# haptic_knob.net
KiCad netlist of a schematic drawn in EasyEDA Pro
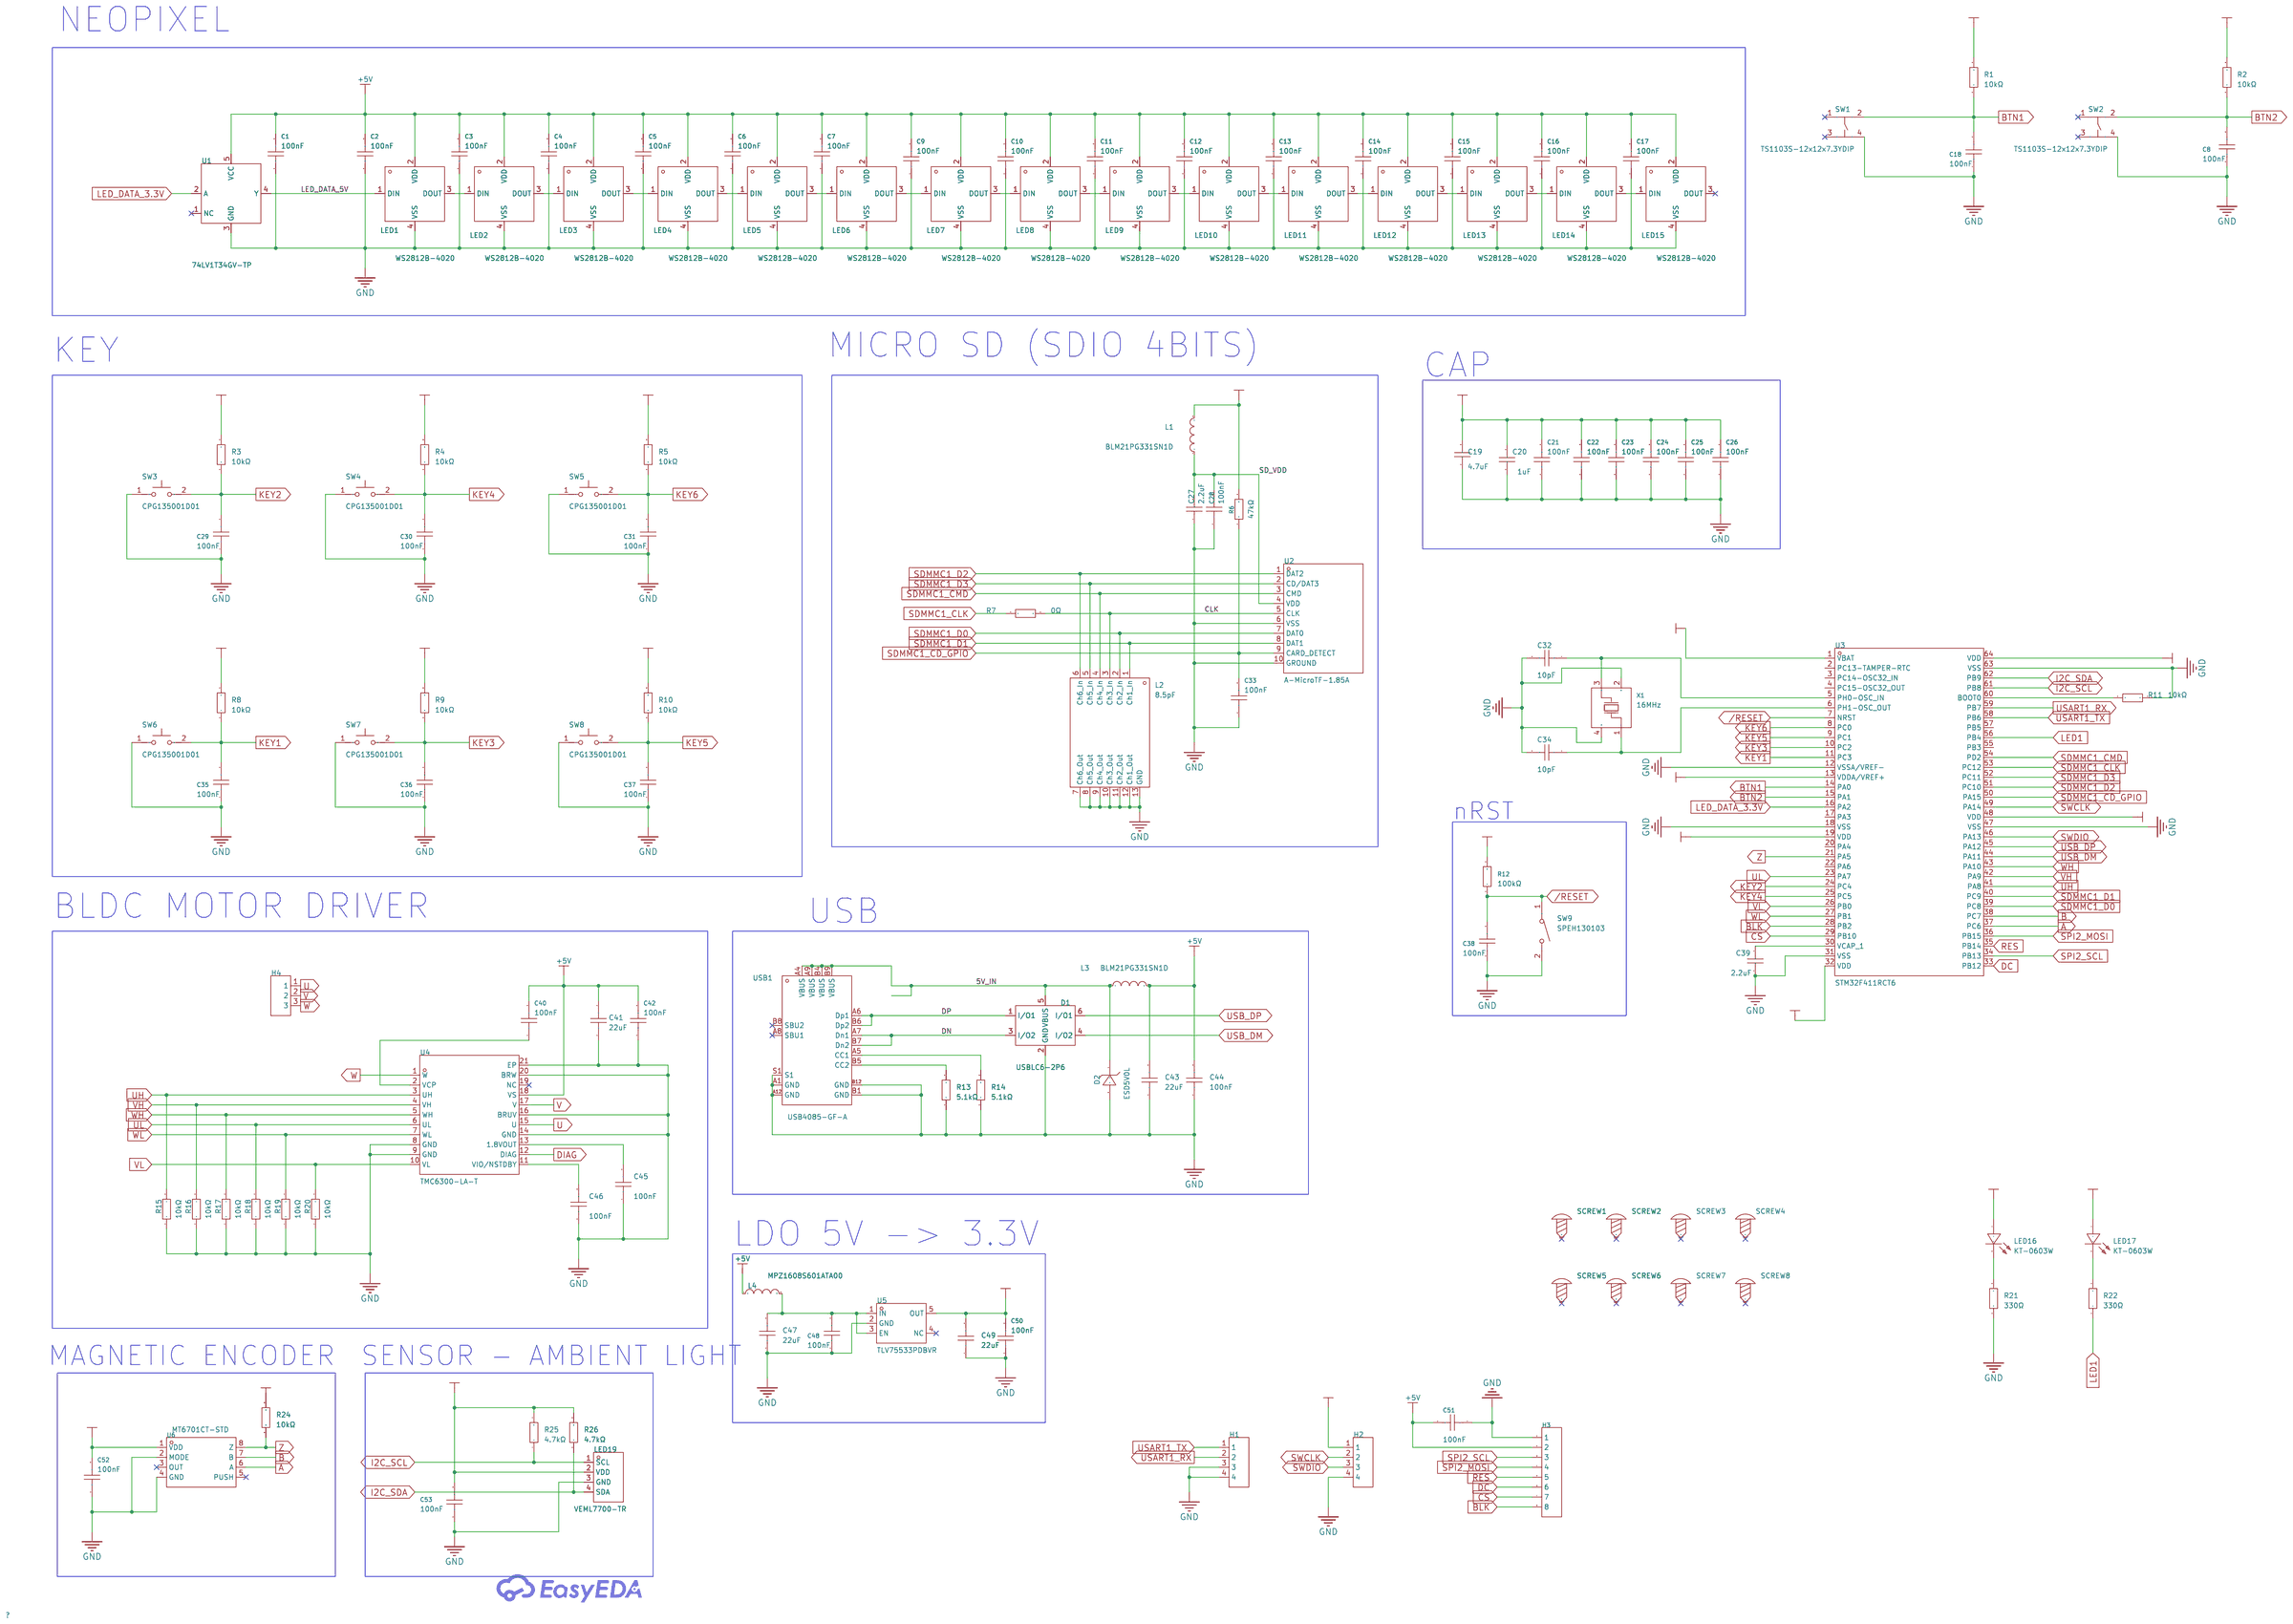
[diagram p0: schematic sheet]

(export (version "E")
  (design (tool "Eeschema 10.0.6"))
  (components
    (comp (ref "C1")
      (value "100nF")
      (fields
        (field (name "Manufacturer Part") "CC0603KRX7R9BB104")
        (field (name "Manufacturer") "YAGEO(国巨)")
      )
      (libsource (lib "easyedapro") (part "CL10B104KB8NNNC"))
    )
    (comp (ref "C2")
      (value "100nF")
      (fields
        (field (name "Manufacturer Part") "CC0603KRX7R9BB104")
        (field (name "Manufacturer") "YAGEO(国巨)")
      )
      (libsource (lib "easyedapro") (part "CL10B104KB8NNNC"))
    )
    (comp (ref "C3")
      (value "100nF")
      (fields
        (field (name "Manufacturer Part") "CC0603KRX7R9BB104")
        (field (name "Manufacturer") "YAGEO(国巨)")
      )
      (libsource (lib "easyedapro") (part "CL10B104KB8NNNC"))
    )
    (comp (ref "C4")
      (value "100nF")
      (fields
        (field (name "Manufacturer Part") "CC0603KRX7R9BB104")
        (field (name "Manufacturer") "YAGEO(国巨)")
      )
      (libsource (lib "easyedapro") (part "CL10B104KB8NNNC"))
    )
    (comp (ref "C5")
      (value "100nF")
      (fields
        (field (name "Manufacturer Part") "CC0603KRX7R9BB104")
        (field (name "Manufacturer") "YAGEO(国巨)")
      )
      (libsource (lib "easyedapro") (part "CL10B104KB8NNNC"))
    )
    (comp (ref "C6")
      (value "100nF")
      (fields
        (field (name "Manufacturer Part") "CC0603KRX7R9BB104")
        (field (name "Manufacturer") "YAGEO(国巨)")
      )
      (libsource (lib "easyedapro") (part "CL10B104KB8NNNC"))
    )
    (comp (ref "C7")
      (value "100nF")
      (fields
        (field (name "Manufacturer Part") "CC0603KRX7R9BB104")
        (field (name "Manufacturer") "YAGEO(国巨)")
      )
      (libsource (lib "easyedapro") (part "CL10B104KB8NNNC"))
    )
    (comp (ref "C8")
      (value "100nF")
      (fields
        (field (name "Manufacturer Part") "CC0603KRX7R9BB104")
        (field (name "Manufacturer") "YAGEO(国巨)")
      )
      (libsource (lib "easyedapro") (part "CL10B104KB8NNNC"))
    )
    (comp (ref "C9")
      (value "100nF")
      (fields
        (field (name "Manufacturer Part") "CC0603KRX7R9BB104")
        (field (name "Manufacturer") "YAGEO(国巨)")
      )
      (libsource (lib "easyedapro") (part "CL10B104KB8NNNC"))
    )
    (comp (ref "C10")
      (value "100nF")
      (fields
        (field (name "Manufacturer Part") "CC0603KRX7R9BB104")
        (field (name "Manufacturer") "YAGEO(国巨)")
      )
      (libsource (lib "easyedapro") (part "CL10B104KB8NNNC"))
    )
    (comp (ref "C11")
      (value "100nF")
      (fields
        (field (name "Manufacturer Part") "CC0603KRX7R9BB104")
        (field (name "Manufacturer") "YAGEO(国巨)")
      )
      (libsource (lib "easyedapro") (part "CL10B104KB8NNNC"))
    )
    (comp (ref "C12")
      (value "100nF")
      (fields
        (field (name "Manufacturer Part") "CC0603KRX7R9BB104")
        (field (name "Manufacturer") "YAGEO(国巨)")
      )
      (libsource (lib "easyedapro") (part "CL10B104KB8NNNC"))
    )
    (comp (ref "C13")
      (value "100nF")
      (fields
        (field (name "Manufacturer Part") "CC0603KRX7R9BB104")
        (field (name "Manufacturer") "YAGEO(国巨)")
      )
      (libsource (lib "easyedapro") (part "CL10B104KB8NNNC"))
    )
    (comp (ref "C14")
      (value "100nF")
      (fields
        (field (name "Manufacturer Part") "CC0603KRX7R9BB104")
        (field (name "Manufacturer") "YAGEO(国巨)")
      )
      (libsource (lib "easyedapro") (part "CL10B104KB8NNNC"))
    )
    (comp (ref "C15")
      (value "100nF")
      (fields
        (field (name "Manufacturer Part") "CC0603KRX7R9BB104")
        (field (name "Manufacturer") "YAGEO(国巨)")
      )
      (libsource (lib "easyedapro") (part "CL10B104KB8NNNC"))
    )
    (comp (ref "C16")
      (value "100nF")
      (fields
        (field (name "Manufacturer Part") "CC0603KRX7R9BB104")
        (field (name "Manufacturer") "YAGEO(国巨)")
      )
      (libsource (lib "easyedapro") (part "CL10B104KB8NNNC"))
    )
    (comp (ref "C17")
      (value "100nF")
      (fields
        (field (name "Manufacturer Part") "CC0603KRX7R9BB104")
        (field (name "Manufacturer") "YAGEO(国巨)")
      )
      (libsource (lib "easyedapro") (part "CL10B104KB8NNNC"))
    )
    (comp (ref "C18")
      (value "100nF")
      (fields
        (field (name "Manufacturer Part") "CC0603KRX7R9BB104")
        (field (name "Manufacturer") "YAGEO(国巨)")
      )
      (libsource (lib "easyedapro") (part "CL10B104KB8NNNC"))
    )
    (comp (ref "C19")
      (value "4.7uF")
      (footprint "easyedapro:C0603")
      (fields
        (field (name "Manufacturer Part") "CL10A475KO8NNNC")
        (field (name "Manufacturer") "SAMSUNG(三星)")
      )
      (libsource (lib "easyedapro") (part "CL10A475KO8NNNC"))
    )
    (comp (ref "C20")
      (value "1uF")
      (footprint "easyedapro:C0603")
      (description "Capacitance:1uF Tolerance:±10% Tolerance:±10% Voltage Rating:25V Temperature Coefficient:X5R")
      (fields
        (field (name "Manufacturer Part") "CL10A105KA8NNNC")
        (field (name "Manufacturer") "SAMSUNG(三星)")
      )
      (libsource (lib "easyedapro") (part "CL10A105KA8NNNC"))
    )
    (comp (ref "C21")
      (value "100nF")
      (fields
        (field (name "Manufacturer Part") "CC0603KRX7R9BB104")
        (field (name "Manufacturer") "YAGEO(国巨)")
      )
      (libsource (lib "easyedapro") (part "CL10B104KB8NNNC"))
    )
    (comp (ref "C22")
      (value "100nF")
      (fields
        (field (name "Manufacturer Part") "CC0603KRX7R9BB104")
        (field (name "Manufacturer") "YAGEO(国巨)")
      )
      (libsource (lib "easyedapro") (part "CL10B104KB8NNNC"))
    )
    (comp (ref "C23")
      (value "100nF")
      (fields
        (field (name "Manufacturer Part") "CC0603KRX7R9BB104")
        (field (name "Manufacturer") "YAGEO(国巨)")
      )
      (libsource (lib "easyedapro") (part "CL10B104KB8NNNC"))
    )
    (comp (ref "C24")
      (value "100nF")
      (fields
        (field (name "Manufacturer Part") "CC0603KRX7R9BB104")
        (field (name "Manufacturer") "YAGEO(国巨)")
      )
      (libsource (lib "easyedapro") (part "CL10B104KB8NNNC"))
    )
    (comp (ref "C25")
      (value "100nF")
      (fields
        (field (name "Manufacturer Part") "CC0603KRX7R9BB104")
        (field (name "Manufacturer") "YAGEO(国巨)")
      )
      (libsource (lib "easyedapro") (part "CL10B104KB8NNNC"))
    )
    (comp (ref "C26")
      (value "100nF")
      (fields
        (field (name "Manufacturer Part") "CC0603KRX7R9BB104")
        (field (name "Manufacturer") "YAGEO(国巨)")
      )
      (libsource (lib "easyedapro") (part "CL10B104KB8NNNC"))
    )
    (comp (ref "C27")
      (value "2.2uF")
      (footprint "easyedapro:C0603")
      (fields
        (field (name "Manufacturer Part") "CL10A225KO8NNNC")
        (field (name "Manufacturer") "SAMSUNG(三星)")
      )
      (libsource (lib "easyedapro") (part "CL10A225KO8NNNC"))
    )
    (comp (ref "C28")
      (value "100nF")
      (fields
        (field (name "Manufacturer Part") "CC0603KRX7R9BB104")
        (field (name "Manufacturer") "YAGEO(国巨)")
      )
      (libsource (lib "easyedapro") (part "CL10B104KB8NNNC"))
    )
    (comp (ref "C29")
      (value "100nF")
      (fields
        (field (name "Manufacturer Part") "CC0603KRX7R9BB104")
        (field (name "Manufacturer") "YAGEO(国巨)")
      )
      (libsource (lib "easyedapro") (part "CL10B104KB8NNNC"))
    )
    (comp (ref "C30")
      (value "100nF")
      (fields
        (field (name "Manufacturer Part") "CC0603KRX7R9BB104")
        (field (name "Manufacturer") "YAGEO(国巨)")
      )
      (libsource (lib "easyedapro") (part "CL10B104KB8NNNC"))
    )
    (comp (ref "C31")
      (value "100nF")
      (fields
        (field (name "Manufacturer Part") "CC0603KRX7R9BB104")
        (field (name "Manufacturer") "YAGEO(国巨)")
      )
      (libsource (lib "easyedapro") (part "CL10B104KB8NNNC"))
    )
    (comp (ref "C32")
      (value "10pF")
      (footprint "easyedapro:C0201")
      (fields
        (field (name "Manufacturer Part") "CL05C100JB5NNNC")
        (field (name "Manufacturer") "SAMSUNG(三星)")
      )
      (libsource (lib "easyedapro") (part "CAP"))
    )
    (comp (ref "C33")
      (value "100nF")
      (fields
        (field (name "Manufacturer Part") "CC0603KRX7R9BB104")
        (field (name "Manufacturer") "YAGEO(国巨)")
      )
      (libsource (lib "easyedapro") (part "CL10B104KB8NNNC"))
    )
    (comp (ref "C34")
      (value "10pF")
      (footprint "easyedapro:C0201")
      (fields
        (field (name "Manufacturer Part") "CL05C100JB5NNNC")
        (field (name "Manufacturer") "SAMSUNG(三星)")
      )
      (libsource (lib "easyedapro") (part "CAP"))
    )
    (comp (ref "C35")
      (value "100nF")
      (fields
        (field (name "Manufacturer Part") "CC0603KRX7R9BB104")
        (field (name "Manufacturer") "YAGEO(国巨)")
      )
      (libsource (lib "easyedapro") (part "CL10B104KB8NNNC"))
    )
    (comp (ref "C36")
      (value "100nF")
      (fields
        (field (name "Manufacturer Part") "CC0603KRX7R9BB104")
        (field (name "Manufacturer") "YAGEO(国巨)")
      )
      (libsource (lib "easyedapro") (part "CL10B104KB8NNNC"))
    )
    (comp (ref "C37")
      (value "100nF")
      (fields
        (field (name "Manufacturer Part") "CC0603KRX7R9BB104")
        (field (name "Manufacturer") "YAGEO(国巨)")
      )
      (libsource (lib "easyedapro") (part "CL10B104KB8NNNC"))
    )
    (comp (ref "C38")
      (value "100nF")
      (fields
        (field (name "Manufacturer Part") "CC0603KRX7R9BB104")
        (field (name "Manufacturer") "YAGEO(国巨)")
      )
      (libsource (lib "easyedapro") (part "CL10B104KB8NNNC"))
    )
    (comp (ref "C39")
      (value "2.2uF")
      (footprint "easyedapro:C0603")
      (fields
        (field (name "Manufacturer Part") "CL10A225KO8NNNC")
        (field (name "Manufacturer") "SAMSUNG(三星)")
      )
      (libsource (lib "easyedapro") (part "CL10A225KO8NNNC"))
    )
    (comp (ref "C40")
      (value "100nF")
      (description "Capacitance:100nF Tolerance:±10% Tolerance:±10% Voltage Rating:50V Temperature Coefficient:X7R")
      (fields
        (field (name "Manufacturer Part") "CL21B104KBCNNNC")
        (field (name "Manufacturer") "SAMSUNG(三星)")
      )
      (libsource (lib "easyedapro") (part "CL10B104KB8NNNC"))
    )
    (comp (ref "C41")
      (value "22uF")
      (footprint "easyedapro:C0805")
      (fields
        (field (name "Manufacturer Part") "CL21A226MAQNNNE")
        (field (name "Manufacturer") "SAMSUNG(三星)")
      )
      (libsource (lib "easyedapro") (part "CL21A226MAQNNNE"))
    )
    (comp (ref "C42")
      (value "100nF")
      (description "Capacitance:100nF Tolerance:±10% Tolerance:±10% Voltage Rating:50V Temperature Coefficient:X7R")
      (fields
        (field (name "Manufacturer Part") "CL21B104KBCNNNC")
        (field (name "Manufacturer") "SAMSUNG(三星)")
      )
      (libsource (lib "easyedapro") (part "CL10B104KB8NNNC"))
    )
    (comp (ref "C43")
      (value "22uF")
      (footprint "easyedapro:C0805")
      (fields
        (field (name "Manufacturer Part") "CL21A226MAQNNNE")
        (field (name "Manufacturer") "SAMSUNG(三星)")
      )
      (libsource (lib "easyedapro") (part "CL21A226MAQNNNE"))
    )
    (comp (ref "C44")
      (value "100nF")
      (footprint "easyedapro:C0603")
      (description "Capacitance:100nF Tolerance:±10% Tolerance:±10% Voltage Rating:16V Temperature Coefficient:X7R")
      (fields
        (field (name "Manufacturer Part") "TCC0603X7R104K160CT")
        (field (name "Manufacturer") "CCTC(三环)")
      )
      (libsource (lib "easyedapro") (part "TCC0603X7R104K160CT"))
    )
    (comp (ref "C45")
      (value "100nF")
      (footprint "easyedapro:C0603")
      (description "Capacitance:100nF Tolerance:±10% Tolerance:±10% Voltage Rating:16V Temperature Coefficient:X7R")
      (fields
        (field (name "Manufacturer Part") "TCC0603X7R104K160CT")
        (field (name "Manufacturer") "CCTC(三环)")
      )
      (libsource (lib "easyedapro") (part "TCC0603X7R104K160CT"))
    )
    (comp (ref "C46")
      (value "100nF")
      (footprint "easyedapro:C0603")
      (description "Capacitance:100nF Tolerance:±10% Tolerance:±10% Voltage Rating:16V Temperature Coefficient:X7R")
      (fields
        (field (name "Manufacturer Part") "TCC0603X7R104K160CT")
        (field (name "Manufacturer") "CCTC(三环)")
      )
      (libsource (lib "easyedapro") (part "TCC0603X7R104K160CT"))
    )
    (comp (ref "C47")
      (value "22uF")
      (footprint "easyedapro:C0805")
      (fields
        (field (name "Manufacturer Part") "CL21A226MAQNNNE")
        (field (name "Manufacturer") "SAMSUNG(三星)")
      )
      (libsource (lib "easyedapro") (part "CL21A226MAQNNNE"))
    )
    (comp (ref "C48")
      (value "100nF")
      (fields
        (field (name "Manufacturer Part") "CC0603KRX7R9BB104")
        (field (name "Manufacturer") "YAGEO(国巨)")
      )
      (libsource (lib "easyedapro") (part "CL10B104KB8NNNC"))
    )
    (comp (ref "C49")
      (value "22uF")
      (footprint "easyedapro:C0805")
      (fields
        (field (name "Manufacturer Part") "CL21A226MAQNNNE")
        (field (name "Manufacturer") "SAMSUNG(三星)")
      )
      (libsource (lib "easyedapro") (part "CL21A226MAQNNNE"))
    )
    (comp (ref "C50")
      (value "100nF")
      (fields
        (field (name "Manufacturer Part") "CC0603KRX7R9BB104")
        (field (name "Manufacturer") "YAGEO(国巨)")
      )
      (libsource (lib "easyedapro") (part "CL10B104KB8NNNC"))
    )
    (comp (ref "C51")
      (value "100nF")
      (fields
        (field (name "Manufacturer Part") "CC0603KRX7R9BB104")
        (field (name "Manufacturer") "YAGEO(国巨)")
      )
      (libsource (lib "easyedapro") (part "CL10B104KB8NNNC"))
    )
    (comp (ref "C52")
      (value "100nF")
      (fields
        (field (name "Manufacturer Part") "CC0603KRX7R9BB104")
        (field (name "Manufacturer") "YAGEO(国巨)")
      )
      (libsource (lib "easyedapro") (part "CL10B104KB8NNNC"))
    )
    (comp (ref "C53")
      (value "100nF")
      (fields
        (field (name "Manufacturer Part") "CC0603KRX7R9BB104")
        (field (name "Manufacturer") "YAGEO(国巨)")
      )
      (libsource (lib "easyedapro") (part "CL10B104KB8NNNC"))
    )
    (comp (ref "D1")
      (value "USBLC6-2P6")
      (footprint "easyedapro:SOT-563_L1.6-W1.2-P0.50-LS1.6-BL")
      (fields (field (name "Manufacturer") "R+O(宏嘉诚)"))
      (libsource (lib "easyedapro") (part "USBLC6-2P6_C49451919"))
    )
    (comp (ref "D2")
      (value "ESD5V0L")
      (footprint "easyedapro:DFN1006-2L_L1.0-W0.6-P0.65-RD")
      (fields (field (name "Manufacturer") "YANGJIE(扬杰)"))
      (libsource (lib "easyedapro") (part "ESD5V0L"))
    )
    (comp (ref "H1")
      (value "~")
      (footprint "easyedapro:HDR-TH_4P-P2.54-V-M")
      (libsource (lib "easyedapro") (part "PZ254V-11-04P"))
    )
    (comp (ref "H2")
      (value "~")
      (footprint "easyedapro:HDR-TH_4P-P2.54-V-M")
      (libsource (lib "easyedapro") (part "PZ254V-11-04P"))
    )
    (comp (ref "H3")
      (value "~")
      (footprint "easyedapro:HDR-TH_8P-P2.54-V-F-1")
      (libsource (lib "easyedapro") (part "Header-Female-2.54_1x8"))
    )
    (comp (ref "H4")
      (value "~")
      (footprint "easyedapro:HDR-TH_3P-P2.54-V-M")
      (libsource (lib "easyedapro") (part "PZ254V-11-03P_C2937625"))
    )
    (comp (ref "L1")
      (value "BLM21PG331SN1D")
      (footprint "easyedapro:L0805")
      (fields (field (name "Manufacturer") "muRata(村田)"))
      (libsource (lib "easyedapro") (part "BLM21PG331SN1D"))
    )
    (comp (ref "L2")
      (value "8.5pF")
      (footprint "easyedapro:DFN-12_L2.5-W1.4-P0.40-BL-EP")
      (fields (field (name "Manufacturer Part") "TPD6F003DQDR") (field (name "Manufacturer") "TI(德州仪器)"))
      (libsource (lib "easyedapro") (part "TPD6F003DQDR"))
    )
    (comp (ref "L3")
      (value "BLM21PG331SN1D")
      (footprint "easyedapro:L0805")
      (fields (field (name "Manufacturer") "muRata(村田)"))
      (libsource (lib "easyedapro") (part "BLM21PG331SN1D"))
    )
    (comp (ref "L4")
      (value "MPZ1608S601ATA00")
      (footprint "easyedapro:L0603")
      (fields (field (name "Manufacturer") "TDK"))
      (libsource (lib "easyedapro") (part "MPZ1608S601ATA00"))
    )
    (comp (ref "LED1")
      (value "WS2812B-4020")
      (footprint "easyedapro:LED-SMD_WS2812B-4020")
      (description "Wavelength:620nm~625nm；515nm~525nm；465nm~475nm")
      (fields (field (name "Manufacturer") "worldsemi"))
      (libsource (lib "easyedapro") (part "WS2812B-4020"))
    )
    (comp (ref "LED2")
      (value "WS2812B-4020")
      (footprint "easyedapro:LED-SMD_WS2812B-4020")
      (description "Wavelength:620nm~625nm；515nm~525nm；465nm~475nm")
      (fields (field (name "Manufacturer") "worldsemi"))
      (libsource (lib "easyedapro") (part "WS2812B-4020"))
    )
    (comp (ref "LED3")
      (value "WS2812B-4020")
      (footprint "easyedapro:LED-SMD_WS2812B-4020")
      (description "Wavelength:620nm~625nm；515nm~525nm；465nm~475nm")
      (fields (field (name "Manufacturer") "worldsemi"))
      (libsource (lib "easyedapro") (part "WS2812B-4020"))
    )
    (comp (ref "LED4")
      (value "WS2812B-4020")
      (footprint "easyedapro:LED-SMD_WS2812B-4020")
      (description "Wavelength:620nm~625nm；515nm~525nm；465nm~475nm")
      (fields (field (name "Manufacturer") "worldsemi"))
      (libsource (lib "easyedapro") (part "WS2812B-4020"))
    )
    (comp (ref "LED5")
      (value "WS2812B-4020")
      (footprint "easyedapro:LED-SMD_WS2812B-4020")
      (description "Wavelength:620nm~625nm；515nm~525nm；465nm~475nm")
      (fields (field (name "Manufacturer") "worldsemi"))
      (libsource (lib "easyedapro") (part "WS2812B-4020"))
    )
    (comp (ref "LED6")
      (value "WS2812B-4020")
      (footprint "easyedapro:LED-SMD_WS2812B-4020")
      (description "Wavelength:620nm~625nm；515nm~525nm；465nm~475nm")
      (fields (field (name "Manufacturer") "worldsemi"))
      (libsource (lib "easyedapro") (part "WS2812B-4020"))
    )
    (comp (ref "LED7")
      (value "WS2812B-4020")
      (footprint "easyedapro:LED-SMD_WS2812B-4020")
      (description "Wavelength:620nm~625nm；515nm~525nm；465nm~475nm")
      (fields (field (name "Manufacturer") "worldsemi"))
      (libsource (lib "easyedapro") (part "WS2812B-4020"))
    )
    (comp (ref "LED8")
      (value "WS2812B-4020")
      (footprint "easyedapro:LED-SMD_WS2812B-4020")
      (description "Wavelength:620nm~625nm；515nm~525nm；465nm~475nm")
      (fields (field (name "Manufacturer") "worldsemi"))
      (libsource (lib "easyedapro") (part "WS2812B-4020"))
    )
    (comp (ref "LED9")
      (value "WS2812B-4020")
      (footprint "easyedapro:LED-SMD_WS2812B-4020")
      (description "Wavelength:620nm~625nm；515nm~525nm；465nm~475nm")
      (fields (field (name "Manufacturer") "worldsemi"))
      (libsource (lib "easyedapro") (part "WS2812B-4020"))
    )
    (comp (ref "LED10")
      (value "WS2812B-4020")
      (footprint "easyedapro:LED-SMD_WS2812B-4020")
      (description "Wavelength:620nm~625nm；515nm~525nm；465nm~475nm")
      (fields (field (name "Manufacturer") "worldsemi"))
      (libsource (lib "easyedapro") (part "WS2812B-4020"))
    )
    (comp (ref "LED11")
      (value "WS2812B-4020")
      (footprint "easyedapro:LED-SMD_WS2812B-4020")
      (description "Wavelength:620nm~625nm；515nm~525nm；465nm~475nm")
      (fields (field (name "Manufacturer") "worldsemi"))
      (libsource (lib "easyedapro") (part "WS2812B-4020"))
    )
    (comp (ref "LED12")
      (value "WS2812B-4020")
      (footprint "easyedapro:LED-SMD_WS2812B-4020")
      (description "Wavelength:620nm~625nm；515nm~525nm；465nm~475nm")
      (fields (field (name "Manufacturer") "worldsemi"))
      (libsource (lib "easyedapro") (part "WS2812B-4020"))
    )
    (comp (ref "LED13")
      (value "WS2812B-4020")
      (footprint "easyedapro:LED-SMD_WS2812B-4020")
      (description "Wavelength:620nm~625nm；515nm~525nm；465nm~475nm")
      (fields (field (name "Manufacturer") "worldsemi"))
      (libsource (lib "easyedapro") (part "WS2812B-4020"))
    )
    (comp (ref "LED14")
      (value "WS2812B-4020")
      (footprint "easyedapro:LED-SMD_WS2812B-4020")
      (description "Wavelength:620nm~625nm；515nm~525nm；465nm~475nm")
      (fields (field (name "Manufacturer") "worldsemi"))
      (libsource (lib "easyedapro") (part "WS2812B-4020"))
    )
    (comp (ref "LED15")
      (value "WS2812B-4020")
      (footprint "easyedapro:LED-SMD_WS2812B-4020")
      (description "Wavelength:620nm~625nm；515nm~525nm；465nm~475nm")
      (fields (field (name "Manufacturer") "worldsemi"))
      (libsource (lib "easyedapro") (part "WS2812B-4020"))
    )
    (comp (ref "LED16")
      (value "KT-0603W")
      (footprint "easyedapro:LED0603-R-RD_WHITE")
      (description "Emitted Color:White")
      (fields (field (name "Manufacturer") "KENTO"))
      (libsource (lib "easyedapro") (part "0603White light_C2290"))
    )
    (comp (ref "LED17")
      (value "KT-0603W")
      (footprint "easyedapro:LED0603-R-RD_WHITE")
      (description "Emitted Color:White")
      (fields (field (name "Manufacturer") "KENTO"))
      (libsource (lib "easyedapro") (part "0603White light_C2290"))
    )
    (comp (ref "LED19")
      (value "VEML7700-TR")
      (footprint "easyedapro:LED-SMD_4P-L6.8-W2.4_VEML7700-TR")
      (fields (field (name "Manufacturer") "VISHAY(威世)"))
      (libsource (lib "easyedapro") (part "VEML7700-TR"))
    )
    (comp (ref "R1")
      (value "10kΩ")
      (footprint "easyedapro:R0603")
      (fields (field (name "Manufacturer Part") "RC0603FR-0710KL") (field (name "Manufacturer") "YAGEO(国巨)"))
      (libsource (lib "easyedapro") (part "RC0603FR-0710KL"))
    )
    (comp (ref "R2")
      (value "10kΩ")
      (footprint "easyedapro:R0603")
      (fields (field (name "Manufacturer Part") "RC0603FR-0710KL") (field (name "Manufacturer") "YAGEO(国巨)"))
      (libsource (lib "easyedapro") (part "RC0603FR-0710KL"))
    )
    (comp (ref "R3")
      (value "10kΩ")
      (footprint "easyedapro:R0603")
      (fields (field (name "Manufacturer Part") "RC0603FR-0710KL") (field (name "Manufacturer") "YAGEO(国巨)"))
      (libsource (lib "easyedapro") (part "RC0603FR-0710KL"))
    )
    (comp (ref "R4")
      (value "10kΩ")
      (footprint "easyedapro:R0603")
      (fields (field (name "Manufacturer Part") "RC0603FR-0710KL") (field (name "Manufacturer") "YAGEO(国巨)"))
      (libsource (lib "easyedapro") (part "RC0603FR-0710KL"))
    )
    (comp (ref "R5")
      (value "10kΩ")
      (footprint "easyedapro:R0603")
      (fields (field (name "Manufacturer Part") "RC0603FR-0710KL") (field (name "Manufacturer") "YAGEO(国巨)"))
      (libsource (lib "easyedapro") (part "RC0603FR-0710KL"))
    )
    (comp (ref "R6")
      (value "47kΩ")
      (footprint "easyedapro:R0603")
      (fields
        (field (name "Manufacturer Part") "0603WAJ0473T5E")
        (field (name "Manufacturer") "UNI-ROYAL(厚声)")
      )
      (libsource (lib "easyedapro") (part "0603WAJ0473T5E"))
    )
    (comp (ref "R7")
      (value "0Ω")
      (footprint "easyedapro:R0603")
      (fields (field (name "Manufacturer Part") "RC0603FR-070RL") (field (name "Manufacturer") "YAGEO(国巨)"))
      (libsource (lib "easyedapro") (part "RC0603FR-070RL"))
    )
    (comp (ref "R8")
      (value "10kΩ")
      (footprint "easyedapro:R0603")
      (fields (field (name "Manufacturer Part") "RC0603FR-0710KL") (field (name "Manufacturer") "YAGEO(国巨)"))
      (libsource (lib "easyedapro") (part "RC0603FR-0710KL"))
    )
    (comp (ref "R9")
      (value "10kΩ")
      (footprint "easyedapro:R0603")
      (fields (field (name "Manufacturer Part") "RC0603FR-0710KL") (field (name "Manufacturer") "YAGEO(国巨)"))
      (libsource (lib "easyedapro") (part "RC0603FR-0710KL"))
    )
    (comp (ref "R10")
      (value "10kΩ")
      (footprint "easyedapro:R0603")
      (fields (field (name "Manufacturer Part") "RC0603FR-0710KL") (field (name "Manufacturer") "YAGEO(国巨)"))
      (libsource (lib "easyedapro") (part "RC0603FR-0710KL"))
    )
    (comp (ref "R11")
      (value "10kΩ")
      (footprint "easyedapro:R0603")
      (fields (field (name "Manufacturer Part") "RC0603FR-0710KL") (field (name "Manufacturer") "YAGEO(国巨)"))
      (libsource (lib "easyedapro") (part "RC0603FR-0710KL"))
    )
    (comp (ref "R12")
      (value "100kΩ")
      (footprint "easyedapro:R0603")
      (fields (field (name "Manufacturer Part") "RC0603FR-07100KL") (field (name "Manufacturer") "YAGEO(国巨)"))
      (libsource (lib "easyedapro") (part "RC0603FR-07100KL"))
    )
    (comp (ref "R13")
      (value "5.1kΩ")
      (footprint "easyedapro:R0603")
      (fields
        (field (name "Manufacturer Part") "0603WAF5101T5E")
        (field (name "Manufacturer") "UNI-ROYAL(厚声)")
      )
      (libsource (lib "easyedapro") (part "Res"))
    )
    (comp (ref "R14")
      (value "5.1kΩ")
      (footprint "easyedapro:R0603")
      (fields
        (field (name "Manufacturer Part") "0603WAF5101T5E")
        (field (name "Manufacturer") "UNI-ROYAL(厚声)")
      )
      (libsource (lib "easyedapro") (part "Res"))
    )
    (comp (ref "R15")
      (value "10kΩ")
      (footprint "easyedapro:R0603")
      (fields (field (name "Manufacturer Part") "RC0603FR-0710KL") (field (name "Manufacturer") "YAGEO(国巨)"))
      (libsource (lib "easyedapro") (part "RC0603FR-0710KL"))
    )
    (comp (ref "R16")
      (value "10kΩ")
      (footprint "easyedapro:R0603")
      (fields (field (name "Manufacturer Part") "RC0603FR-0710KL") (field (name "Manufacturer") "YAGEO(国巨)"))
      (libsource (lib "easyedapro") (part "RC0603FR-0710KL"))
    )
    (comp (ref "R17")
      (value "10kΩ")
      (footprint "easyedapro:R0603")
      (fields (field (name "Manufacturer Part") "RC0603FR-0710KL") (field (name "Manufacturer") "YAGEO(国巨)"))
      (libsource (lib "easyedapro") (part "RC0603FR-0710KL"))
    )
    (comp (ref "R18")
      (value "10kΩ")
      (footprint "easyedapro:R0603")
      (fields (field (name "Manufacturer Part") "RC0603FR-0710KL") (field (name "Manufacturer") "YAGEO(国巨)"))
      (libsource (lib "easyedapro") (part "RC0603FR-0710KL"))
    )
    (comp (ref "R19")
      (value "10kΩ")
      (footprint "easyedapro:R0603")
      (fields (field (name "Manufacturer Part") "RC0603FR-0710KL") (field (name "Manufacturer") "YAGEO(国巨)"))
      (libsource (lib "easyedapro") (part "RC0603FR-0710KL"))
    )
    (comp (ref "R20")
      (value "10kΩ")
      (footprint "easyedapro:R0603")
      (fields (field (name "Manufacturer Part") "RC0603FR-0710KL") (field (name "Manufacturer") "YAGEO(国巨)"))
      (libsource (lib "easyedapro") (part "RC0603FR-0710KL"))
    )
    (comp (ref "R21")
      (value "330Ω")
      (footprint "easyedapro:R0603")
      (fields
        (field (name "Manufacturer Part") "0603WAF3300T5E")
        (field (name "Manufacturer") "UNI-ROYAL(厚声)")
      )
      (libsource (lib "easyedapro") (part "0603WAF3300T5E"))
    )
    (comp (ref "R22")
      (value "330Ω")
      (footprint "easyedapro:R0603")
      (fields
        (field (name "Manufacturer Part") "0603WAF3300T5E")
        (field (name "Manufacturer") "UNI-ROYAL(厚声)")
      )
      (libsource (lib "easyedapro") (part "0603WAF3300T5E"))
    )
    (comp (ref "R24")
      (value "10kΩ")
      (footprint "easyedapro:R0603")
      (fields (field (name "Manufacturer Part") "RC0603FR-0710KL") (field (name "Manufacturer") "YAGEO(国巨)"))
      (libsource (lib "easyedapro") (part "RC0603FR-0710KL"))
    )
    (comp (ref "R25")
      (value "4.7kΩ")
      (footprint "easyedapro:R0603")
      (fields
        (field (name "Manufacturer Part") "0603WAF4701T5E")
        (field (name "Manufacturer") "UNI-ROYAL(厚声)")
      )
      (libsource (lib "easyedapro") (part "0603WAF4701T5E"))
    )
    (comp (ref "R26")
      (value "4.7kΩ")
      (footprint "easyedapro:R0603")
      (fields
        (field (name "Manufacturer Part") "0603WAF4701T5E")
        (field (name "Manufacturer") "UNI-ROYAL(厚声)")
      )
      (libsource (lib "easyedapro") (part "0603WAF4701T5E"))
    )
    (comp (ref "SCREW1")
      (value "~")
      (footprint "easyedapro:Screw-Hole-M2")
      (libsource (lib "easyedapro") (part "Screw-Hole"))
    )
    (comp (ref "SCREW2")
      (value "~")
      (footprint "easyedapro:Screw-Hole-M2")
      (libsource (lib "easyedapro") (part "Screw-Hole"))
    )
    (comp (ref "SCREW3")
      (value "~")
      (footprint "easyedapro:Screw-Hole-M2")
      (libsource (lib "easyedapro") (part "Screw-Hole"))
    )
    (comp (ref "SCREW4")
      (value "~")
      (footprint "easyedapro:Screw-Hole-M2")
      (libsource (lib "easyedapro") (part "Screw-Hole"))
    )
    (comp (ref "SCREW5")
      (value "~")
      (footprint "easyedapro:Screw-Hole-M2")
      (libsource (lib "easyedapro") (part "Screw-Hole"))
    )
    (comp (ref "SCREW6")
      (value "~")
      (footprint "easyedapro:Screw-Hole-M2")
      (libsource (lib "easyedapro") (part "Screw-Hole"))
    )
    (comp (ref "SCREW7")
      (value "~")
      (footprint "easyedapro:Screw-Hole-M2")
      (libsource (lib "easyedapro") (part "Screw-Hole"))
    )
    (comp (ref "SCREW8")
      (value "~")
      (footprint "easyedapro:Screw-Hole-M2")
      (libsource (lib "easyedapro") (part "Screw-Hole"))
    )
    (comp (ref "SW1")
      (value "TS1103S-12x12x7.3YDIP")
      (footprint "easyedapro:SW-TH_4P-L12.0-W12.0-P5.00-LS12.5-TL")
      (fields (field (name "Manufacturer") "CAX(创都)"))
      (libsource (lib "easyedapro") (part "TS1103S-12X12X7.3YDIP"))
    )
    (comp (ref "SW2")
      (value "TS1103S-12x12x7.3YDIP")
      (footprint "easyedapro:SW-TH_4P-L12.0-W12.0-P5.00-LS12.5-TL")
      (fields (field (name "Manufacturer") "CAX(创都)"))
      (libsource (lib "easyedapro") (part "TS1103S-12X12X7.3YDIP"))
    )
    (comp (ref "SW3")
      (value "CPG135001D01")
      (footprint "easyedapro:KEY-TH_CPG135001D0X")
      (fields (field (name "Manufacturer") "Kailh(凯华)"))
      (libsource (lib "easyedapro") (part "CPG135001D01"))
    )
    (comp (ref "SW4")
      (value "CPG135001D01")
      (footprint "easyedapro:KEY-TH_CPG135001D0X")
      (fields (field (name "Manufacturer") "Kailh(凯华)"))
      (libsource (lib "easyedapro") (part "CPG135001D01"))
    )
    (comp (ref "SW5")
      (value "CPG135001D01")
      (footprint "easyedapro:KEY-TH_CPG135001D0X")
      (fields (field (name "Manufacturer") "Kailh(凯华)"))
      (libsource (lib "easyedapro") (part "CPG135001D01"))
    )
    (comp (ref "SW6")
      (value "CPG135001D01")
      (footprint "easyedapro:KEY-TH_CPG135001D0X")
      (fields (field (name "Manufacturer") "Kailh(凯华)"))
      (libsource (lib "easyedapro") (part "CPG135001D01"))
    )
    (comp (ref "SW7")
      (value "CPG135001D01")
      (footprint "easyedapro:KEY-TH_CPG135001D0X")
      (fields (field (name "Manufacturer") "Kailh(凯华)"))
      (libsource (lib "easyedapro") (part "CPG135001D01"))
    )
    (comp (ref "SW8")
      (value "CPG135001D01")
      (footprint "easyedapro:KEY-TH_CPG135001D0X")
      (fields (field (name "Manufacturer") "Kailh(凯华)"))
      (libsource (lib "easyedapro") (part "CPG135001D01"))
    )
    (comp (ref "SW9")
      (value "SPEH130103")
      (footprint "easyedapro:SW-SMD_L6.0-W6.0-LS6.6")
      (fields (field (name "Manufacturer") "ALPSALPINE(阿尔卑斯阿尔派)"))
      (libsource (lib "easyedapro") (part "SPEH130103"))
    )
    (comp (ref "U1")
      (value "74LV1T34GV-TP")
      (footprint "easyedapro:SOT-23-5_L2.9-W1.6-P0.95-LS2.8-BR")
      (fields (field (name "Manufacturer") "TECH PUBLIC(台舟)"))
      (libsource (lib "easyedapro") (part "SN74LV1T34DBVR"))
    )
    (comp (ref "U2")
      (value "A-MicroTF-1.85A")
      (footprint "easyedapro:TF-SMD_A-MICROTF-1.85A")
      (fields (field (name "Manufacturer") "MyAntenna(摩天射频)"))
      (libsource (lib "easyedapro") (part "A-MICROTF-1.85A"))
    )
    (comp (ref "U3")
      (value "STM32F411RCT6")
      (footprint "easyedapro:LQFP-64_L10.0-W10.0-P0.50-LS12.0-BL")
      (fields (field (name "Manufacturer") "ST(意法半导体)"))
      (libsource (lib "easyedapro") (part "STM32F411RCT6"))
    )
    (comp (ref "U4")
      (value "TMC6300-LA-T")
      (footprint "easyedapro:QFN-20_L3.0-W3.0-P0.40-BL-EP1.7")
      (fields (field (name "Manufacturer") "TRINAMIC"))
      (libsource (lib "easyedapro") (part "TMC6300-LA-T_C5274455"))
    )
    (comp (ref "U5")
      (value "TLV75533PDBVR")
      (footprint "easyedapro:SOT-23-5_L3.0-W1.7-P0.95-LS2.8-BR")
      (fields (field (name "Manufacturer") "TI(德州仪器)"))
      (libsource (lib "easyedapro") (part "TLV75533PDBVR"))
    )
    (comp (ref "U6")
      (value "MT6701CT-STD")
      (footprint "easyedapro:SOP-8_L4.9-W3.9-P1.27-LS6.0-BL")
      (fields (field (name "Manufacturer") "MagnTek(麦歌恩)"))
      (libsource (lib "easyedapro") (part "MT6701CT-STD"))
    )
    (comp (ref "USB1")
      (value "USB4085-GF-A")
      (footprint "easyedapro:USC-C-SMD_USB4085-GF-A")
      (fields (field (name "Manufacturer") "GCT"))
      (libsource (lib "easyedapro") (part "USB4085-GF-A_C7095263"))
    )
    (comp (ref "X1")
      (value "16MHz")
      (footprint "easyedapro:CRYSTAL-SMD_4P-L2.5-W2.0-BL-A")
      (fields
        (field (name "Manufacturer Part") "NX2520SA-16MHZ-STD-CSW-5")
        (field (name "Manufacturer") "NDK")
      )
      (libsource (lib "easyedapro") (part "STD-CSW-5"))
    )
  )
  (nets
    (net (code "1") (name "+5V") (class "Default")
      (node (ref "C1") (pin "2") (pinfunction "2_2") (pintype "input"))
      (node (ref "C10") (pin "2") (pinfunction "2_2") (pintype "input"))
      (node (ref "C11") (pin "2") (pinfunction "2_2") (pintype "input"))
      (node (ref "C12") (pin "2") (pinfunction "2_2") (pintype "input"))
      (node (ref "C13") (pin "2") (pinfunction "2_2") (pintype "input"))
      (node (ref "C14") (pin "2") (pinfunction "2_2") (pintype "input"))
      (node (ref "C15") (pin "2") (pinfunction "2_2") (pintype "input"))
      (node (ref "C16") (pin "2") (pinfunction "2_2") (pintype "input"))
      (node (ref "C17") (pin "2") (pinfunction "2_2") (pintype "input"))
      (node (ref "C2") (pin "2") (pinfunction "2_2") (pintype "input"))
      (node (ref "C3") (pin "2") (pinfunction "2_2") (pintype "input"))
      (node (ref "C4") (pin "2") (pinfunction "2_2") (pintype "input"))
      (node (ref "C40") (pin "2") (pinfunction "2_2") (pintype "input"))
      (node (ref "C41") (pin "2") (pinfunction "2_2") (pintype "unspecified"))
      (node (ref "C42") (pin "2") (pinfunction "2_2") (pintype "input"))
      (node (ref "C43") (pin "2") (pinfunction "2_2") (pintype "unspecified"))
      (node (ref "C44") (pin "2") (pinfunction "2_2") (pintype "unspecified"))
      (node (ref "C5") (pin "2") (pinfunction "2_2") (pintype "input"))
      (node (ref "C51") (pin "2") (pinfunction "2_2") (pintype "input"))
      (node (ref "C6") (pin "2") (pinfunction "2_2") (pintype "input"))
      (node (ref "C7") (pin "2") (pinfunction "2_2") (pintype "input"))
      (node (ref "C9") (pin "2") (pinfunction "2_2") (pintype "input"))
      (node (ref "H3") (pin "2") (pinfunction "2_2") (pintype "input"))
      (node (ref "L3") (pin "2") (pinfunction "2_2") (pintype "input"))
      (node (ref "L4") (pin "1") (pinfunction "1_1") (pintype "unspecified"))
      (node (ref "LED1") (pin "2") (pinfunction "VDD_2") (pintype "unspecified"))
      (node (ref "LED10") (pin "2") (pinfunction "VDD_2") (pintype "unspecified"))
      (node (ref "LED11") (pin "2") (pinfunction "VDD_2") (pintype "unspecified"))
      (node (ref "LED12") (pin "2") (pinfunction "VDD_2") (pintype "unspecified"))
      (node (ref "LED13") (pin "2") (pinfunction "VDD_2") (pintype "unspecified"))
      (node (ref "LED14") (pin "2") (pinfunction "VDD_2") (pintype "unspecified"))
      (node (ref "LED15") (pin "2") (pinfunction "VDD_2") (pintype "unspecified"))
      (node (ref "LED2") (pin "2") (pinfunction "VDD_2") (pintype "unspecified"))
      (node (ref "LED3") (pin "2") (pinfunction "VDD_2") (pintype "unspecified"))
      (node (ref "LED4") (pin "2") (pinfunction "VDD_2") (pintype "unspecified"))
      (node (ref "LED5") (pin "2") (pinfunction "VDD_2") (pintype "unspecified"))
      (node (ref "LED6") (pin "2") (pinfunction "VDD_2") (pintype "unspecified"))
      (node (ref "LED7") (pin "2") (pinfunction "VDD_2") (pintype "unspecified"))
      (node (ref "LED8") (pin "2") (pinfunction "VDD_2") (pintype "unspecified"))
      (node (ref "LED9") (pin "2") (pinfunction "VDD_2") (pintype "unspecified"))
      (node (ref "U1") (pin "5") (pinfunction "VCC_5") (pintype "unspecified"))
      (node (ref "U4") (pin "18") (pinfunction "VS_18") (pintype "unspecified"))
    )
    (net (code "2") (name "/5V_IN") (class "Default")
      (node (ref "D1") (pin "5") (pinfunction "VBUS_5") (pintype "unspecified"))
      (node (ref "D2") (pin "1") (pinfunction "C_1") (pintype "unspecified"))
      (node (ref "L3") (pin "1") (pinfunction "1_1") (pintype "input"))
      (node (ref "USB1") (pin "A4") (pinfunction "VBUS_A4") (pintype "unspecified"))
      (node (ref "USB1") (pin "A9") (pinfunction "VBUS_A9") (pintype "unspecified"))
      (node (ref "USB1") (pin "B4") (pinfunction "VBUS_B4") (pintype "unspecified"))
      (node (ref "USB1") (pin "B9") (pinfunction "VBUS_B9") (pintype "unspecified"))
    )
    (net (code "3") (name "/CLK") (class "Default")
      (node (ref "L2") (pin "3") (pinfunction "Ch3_In_3") (pintype "unspecified"))
      (node (ref "R7") (pin "2") (pinfunction "2_2") (pintype "input"))
      (node (ref "U2") (pin "5") (pinfunction "CLK_5") (pintype "unspecified"))
    )
    (net (code "4") (name "/DN") (class "Default")
      (node (ref "D1") (pin "3") (pinfunction "I/O2_3") (pintype "unspecified"))
      (node (ref "USB1") (pin "A7") (pinfunction "Dn1_A7") (pintype "unspecified"))
      (node (ref "USB1") (pin "B7") (pinfunction "Dn2_B7") (pintype "unspecified"))
    )
    (net (code "5") (name "/DP") (class "Default")
      (node (ref "D1") (pin "1") (pinfunction "I/O1_1") (pintype "unspecified"))
      (node (ref "USB1") (pin "A6") (pinfunction "Dp1_A6") (pintype "unspecified"))
      (node (ref "USB1") (pin "B6") (pinfunction "Dp2_B6") (pintype "unspecified"))
    )
    (net (code "6") (name "/LED_DATA_5V") (class "Default")
      (node (ref "LED1") (pin "1") (pinfunction "DIN_1") (pintype "unspecified"))
      (node (ref "U1") (pin "4") (pinfunction "Y_4") (pintype "unspecified"))
    )
    (net (code "7") (name "/SD_VDD") (class "Default")
      (node (ref "C27") (pin "2") (pinfunction "2_2") (pintype "input"))
      (node (ref "C28") (pin "2") (pinfunction "2_2") (pintype "input"))
      (node (ref "L1") (pin "1") (pinfunction "1_1") (pintype "input"))
      (node (ref "U2") (pin "4") (pinfunction "VDD_4") (pintype "unspecified"))
    )
    (net (code "8") (name "3.3V") (class "Default")
      (node (ref "C19") (pin "2") (pinfunction "2_2") (pintype "input"))
      (node (ref "C20") (pin "2") (pinfunction "2_2") (pintype "input"))
      (node (ref "C21") (pin "2") (pinfunction "2_2") (pintype "input"))
      (node (ref "C22") (pin "2") (pinfunction "2_2") (pintype "input"))
      (node (ref "C23") (pin "2") (pinfunction "2_2") (pintype "input"))
      (node (ref "C24") (pin "2") (pinfunction "2_2") (pintype "input"))
      (node (ref "C25") (pin "2") (pinfunction "2_2") (pintype "input"))
      (node (ref "C26") (pin "2") (pinfunction "2_2") (pintype "input"))
      (node (ref "C49") (pin "2") (pinfunction "2_2") (pintype "unspecified"))
      (node (ref "C50") (pin "2") (pinfunction "2_2") (pintype "input"))
      (node (ref "C52") (pin "2") (pinfunction "2_2") (pintype "input"))
      (node (ref "C53") (pin "2") (pinfunction "2_2") (pintype "input"))
      (node (ref "H2") (pin "1") (pinfunction "1_1") (pintype "unspecified"))
      (node (ref "L1") (pin "2") (pinfunction "2_2") (pintype "input"))
      (node (ref "LED16") (pin "1") (pinfunction "A_1") (pintype "unspecified"))
      (node (ref "LED17") (pin "1") (pinfunction "A_1") (pintype "unspecified"))
      (node (ref "LED19") (pin "2") (pinfunction "VDD_2") (pintype "unspecified"))
      (node (ref "R1") (pin "2") (pinfunction "2_2") (pintype "input"))
      (node (ref "R10") (pin "2") (pinfunction "2_2") (pintype "input"))
      (node (ref "R12") (pin "2") (pinfunction "2_2") (pintype "input"))
      (node (ref "R2") (pin "2") (pinfunction "2_2") (pintype "input"))
      (node (ref "R24") (pin "2") (pinfunction "2_2") (pintype "input"))
      (node (ref "R25") (pin "2") (pinfunction "2_2") (pintype "input"))
      (node (ref "R26") (pin "2") (pinfunction "2_2") (pintype "input"))
      (node (ref "R3") (pin "2") (pinfunction "2_2") (pintype "input"))
      (node (ref "R4") (pin "2") (pinfunction "2_2") (pintype "input"))
      (node (ref "R5") (pin "2") (pinfunction "2_2") (pintype "input"))
      (node (ref "R6") (pin "2") (pinfunction "2_2") (pintype "input"))
      (node (ref "R8") (pin "2") (pinfunction "2_2") (pintype "input"))
      (node (ref "R9") (pin "2") (pinfunction "2_2") (pintype "input"))
      (node (ref "U3") (pin "1") (pinfunction "VBAT_1") (pintype "unspecified"))
      (node (ref "U3") (pin "13") (pinfunction "VDDA/VREF+_13") (pintype "unspecified"))
      (node (ref "U3") (pin "19") (pinfunction "VDD_19") (pintype "unspecified"))
      (node (ref "U3") (pin "32") (pinfunction "VDD_32") (pintype "unspecified"))
      (node (ref "U3") (pin "48") (pinfunction "VDD_48") (pintype "unspecified"))
      (node (ref "U3") (pin "64") (pinfunction "VDD_64") (pintype "unspecified"))
      (node (ref "U5") (pin "5") (pinfunction "OUT_5") (pintype "unspecified"))
      (node (ref "U6") (pin "1") (pinfunction "VDD_1") (pintype "input"))
    )
    (net (code "9") (name "A") (class "Default")
      (node (ref "U3") (pin "37") (pinfunction "PC6_37") (pintype "unspecified"))
      (node (ref "U6") (pin "6") (pinfunction "A_6") (pintype "input"))
    )
    (net (code "10") (name "B") (class "Default")
      (node (ref "U3") (pin "38") (pinfunction "PC7_38") (pintype "unspecified"))
      (node (ref "U6") (pin "7") (pinfunction "B_7") (pintype "input"))
    )
    (net (code "11") (name "BLK") (class "Default")
      (node (ref "H3") (pin "8") (pinfunction "8_8") (pintype "input"))
      (node (ref "U3") (pin "28") (pinfunction "PB2_28") (pintype "unspecified"))
    )
    (net (code "12") (name "BTN1") (class "Default")
      (node (ref "C18") (pin "2") (pinfunction "2_2") (pintype "input"))
      (node (ref "R1") (pin "1") (pinfunction "1_1") (pintype "input"))
      (node (ref "SW1") (pin "2") (pinfunction "2_2") (pintype "unspecified"))
      (node (ref "U3") (pin "14") (pinfunction "PA0_14") (pintype "unspecified"))
    )
    (net (code "13") (name "BTN2") (class "Default")
      (node (ref "C8") (pin "2") (pinfunction "2_2") (pintype "input"))
      (node (ref "R2") (pin "1") (pinfunction "1_1") (pintype "input"))
      (node (ref "SW2") (pin "2") (pinfunction "2_2") (pintype "unspecified"))
      (node (ref "U3") (pin "15") (pinfunction "PA1_15") (pintype "unspecified"))
    )
    (net (code "14") (name "CS") (class "Default")
      (node (ref "H3") (pin "7") (pinfunction "7_7") (pintype "input"))
      (node (ref "U3") (pin "29") (pinfunction "PB10_29") (pintype "unspecified"))
    )
    (net (code "15") (name "DC") (class "Default")
      (node (ref "H3") (pin "6") (pinfunction "6_6") (pintype "input"))
      (node (ref "U3") (pin "33") (pinfunction "PB12_33") (pintype "unspecified"))
    )
    (net (code "16") (name "DIAG") (class "Default")
      (node (ref "U4") (pin "12") (pinfunction "DIAG_12") (pintype "unspecified"))
    )
    (net (code "17") (name "GND") (class "Default")
      (node (ref "C1") (pin "1") (pinfunction "1_1") (pintype "input"))
      (node (ref "C10") (pin "1") (pinfunction "1_1") (pintype "input"))
      (node (ref "C11") (pin "1") (pinfunction "1_1") (pintype "input"))
      (node (ref "C12") (pin "1") (pinfunction "1_1") (pintype "input"))
      (node (ref "C13") (pin "1") (pinfunction "1_1") (pintype "input"))
      (node (ref "C14") (pin "1") (pinfunction "1_1") (pintype "input"))
      (node (ref "C15") (pin "1") (pinfunction "1_1") (pintype "input"))
      (node (ref "C16") (pin "1") (pinfunction "1_1") (pintype "input"))
      (node (ref "C17") (pin "1") (pinfunction "1_1") (pintype "input"))
      (node (ref "C18") (pin "1") (pinfunction "1_1") (pintype "input"))
      (node (ref "C19") (pin "1") (pinfunction "1_1") (pintype "input"))
      (node (ref "C2") (pin "1") (pinfunction "1_1") (pintype "input"))
      (node (ref "C20") (pin "1") (pinfunction "1_1") (pintype "input"))
      (node (ref "C21") (pin "1") (pinfunction "1_1") (pintype "input"))
      (node (ref "C22") (pin "1") (pinfunction "1_1") (pintype "input"))
      (node (ref "C23") (pin "1") (pinfunction "1_1") (pintype "input"))
      (node (ref "C24") (pin "1") (pinfunction "1_1") (pintype "input"))
      (node (ref "C25") (pin "1") (pinfunction "1_1") (pintype "input"))
      (node (ref "C26") (pin "1") (pinfunction "1_1") (pintype "input"))
      (node (ref "C27") (pin "1") (pinfunction "1_1") (pintype "input"))
      (node (ref "C28") (pin "1") (pinfunction "1_1") (pintype "input"))
      (node (ref "C29") (pin "1") (pinfunction "1_1") (pintype "input"))
      (node (ref "C3") (pin "1") (pinfunction "1_1") (pintype "input"))
      (node (ref "C30") (pin "1") (pinfunction "1_1") (pintype "input"))
      (node (ref "C31") (pin "1") (pinfunction "1_1") (pintype "input"))
      (node (ref "C32") (pin "2") (pinfunction "2_2") (pintype "input"))
      (node (ref "C33") (pin "1") (pinfunction "1_1") (pintype "input"))
      (node (ref "C34") (pin "2") (pinfunction "2_2") (pintype "input"))
      (node (ref "C35") (pin "1") (pinfunction "1_1") (pintype "input"))
      (node (ref "C36") (pin "1") (pinfunction "1_1") (pintype "input"))
      (node (ref "C37") (pin "1") (pinfunction "1_1") (pintype "input"))
      (node (ref "C38") (pin "1") (pinfunction "1_1") (pintype "input"))
      (node (ref "C39") (pin "1") (pinfunction "1_1") (pintype "input"))
      (node (ref "C4") (pin "1") (pinfunction "1_1") (pintype "input"))
      (node (ref "C41") (pin "1") (pinfunction "1_1") (pintype "unspecified"))
      (node (ref "C42") (pin "1") (pinfunction "1_1") (pintype "input"))
      (node (ref "C43") (pin "1") (pinfunction "1_1") (pintype "unspecified"))
      (node (ref "C44") (pin "1") (pinfunction "1_1") (pintype "unspecified"))
      (node (ref "C45") (pin "1") (pinfunction "1_1") (pintype "unspecified"))
      (node (ref "C46") (pin "1") (pinfunction "1_1") (pintype "unspecified"))
      (node (ref "C47") (pin "1") (pinfunction "1_1") (pintype "unspecified"))
      (node (ref "C48") (pin "1") (pinfunction "1_1") (pintype "input"))
      (node (ref "C49") (pin "1") (pinfunction "1_1") (pintype "unspecified"))
      (node (ref "C5") (pin "1") (pinfunction "1_1") (pintype "input"))
      (node (ref "C50") (pin "1") (pinfunction "1_1") (pintype "input"))
      (node (ref "C51") (pin "1") (pinfunction "1_1") (pintype "input"))
      (node (ref "C52") (pin "1") (pinfunction "1_1") (pintype "input"))
      (node (ref "C53") (pin "1") (pinfunction "1_1") (pintype "input"))
      (node (ref "C6") (pin "1") (pinfunction "1_1") (pintype "input"))
      (node (ref "C7") (pin "1") (pinfunction "1_1") (pintype "input"))
      (node (ref "C8") (pin "1") (pinfunction "1_1") (pintype "input"))
      (node (ref "C9") (pin "1") (pinfunction "1_1") (pintype "input"))
      (node (ref "D1") (pin "2") (pinfunction "GND_2") (pintype "unspecified"))
      (node (ref "D2") (pin "2") (pinfunction "A_2") (pintype "unspecified"))
      (node (ref "H1") (pin "3") (pinfunction "3_3") (pintype "unspecified"))
      (node (ref "H1") (pin "4") (pinfunction "4_4") (pintype "unspecified"))
      (node (ref "H2") (pin "4") (pinfunction "4_4") (pintype "unspecified"))
      (node (ref "H3") (pin "1") (pinfunction "1_1") (pintype "input"))
      (node (ref "L2") (pin "10") (pinfunction "Ch3_Out_10") (pintype "unspecified"))
      (node (ref "L2") (pin "11") (pinfunction "Ch2_Out_11") (pintype "unspecified"))
      (node (ref "L2") (pin "12") (pinfunction "Ch1_Out_12") (pintype "unspecified"))
      (node (ref "L2") (pin "13") (pinfunction "GND_13") (pintype "unspecified"))
      (node (ref "L2") (pin "7") (pinfunction "Ch6_Out_7") (pintype "unspecified"))
      (node (ref "L2") (pin "8") (pinfunction "Ch5_Out_8") (pintype "unspecified"))
      (node (ref "L2") (pin "9") (pinfunction "Ch4_Out_9") (pintype "unspecified"))
      (node (ref "LED1") (pin "4") (pinfunction "VSS_4") (pintype "unspecified"))
      (node (ref "LED10") (pin "4") (pinfunction "VSS_4") (pintype "unspecified"))
      (node (ref "LED11") (pin "4") (pinfunction "VSS_4") (pintype "unspecified"))
      (node (ref "LED12") (pin "4") (pinfunction "VSS_4") (pintype "unspecified"))
      (node (ref "LED13") (pin "4") (pinfunction "VSS_4") (pintype "unspecified"))
      (node (ref "LED14") (pin "4") (pinfunction "VSS_4") (pintype "unspecified"))
      (node (ref "LED15") (pin "4") (pinfunction "VSS_4") (pintype "unspecified"))
      (node (ref "LED19") (pin "3") (pinfunction "GND_3") (pintype "unspecified"))
      (node (ref "LED2") (pin "4") (pinfunction "VSS_4") (pintype "unspecified"))
      (node (ref "LED3") (pin "4") (pinfunction "VSS_4") (pintype "unspecified"))
      (node (ref "LED4") (pin "4") (pinfunction "VSS_4") (pintype "unspecified"))
      (node (ref "LED5") (pin "4") (pinfunction "VSS_4") (pintype "unspecified"))
      (node (ref "LED6") (pin "4") (pinfunction "VSS_4") (pintype "unspecified"))
      (node (ref "LED7") (pin "4") (pinfunction "VSS_4") (pintype "unspecified"))
      (node (ref "LED8") (pin "4") (pinfunction "VSS_4") (pintype "unspecified"))
      (node (ref "LED9") (pin "4") (pinfunction "VSS_4") (pintype "unspecified"))
      (node (ref "R11") (pin "1") (pinfunction "1_1") (pintype "input"))
      (node (ref "R13") (pin "1") (pinfunction "1_1") (pintype "input"))
      (node (ref "R14") (pin "1") (pinfunction "1_1") (pintype "input"))
      (node (ref "R15") (pin "1") (pinfunction "1_1") (pintype "input"))
      (node (ref "R16") (pin "1") (pinfunction "1_1") (pintype "input"))
      (node (ref "R17") (pin "1") (pinfunction "1_1") (pintype "input"))
      (node (ref "R18") (pin "1") (pinfunction "1_1") (pintype "input"))
      (node (ref "R19") (pin "1") (pinfunction "1_1") (pintype "input"))
      (node (ref "R20") (pin "1") (pinfunction "1_1") (pintype "input"))
      (node (ref "R21") (pin "1") (pinfunction "1_1") (pintype "input"))
      (node (ref "SW1") (pin "4") (pinfunction "4_4") (pintype "unspecified"))
      (node (ref "SW2") (pin "4") (pinfunction "4_4") (pintype "unspecified"))
      (node (ref "SW3") (pin "1") (pinfunction "1_1") (pintype "unspecified"))
      (node (ref "SW4") (pin "1") (pinfunction "1_1") (pintype "unspecified"))
      (node (ref "SW5") (pin "1") (pinfunction "1_1") (pintype "unspecified"))
      (node (ref "SW6") (pin "1") (pinfunction "1_1") (pintype "unspecified"))
      (node (ref "SW7") (pin "1") (pinfunction "1_1") (pintype "unspecified"))
      (node (ref "SW8") (pin "1") (pinfunction "1_1") (pintype "unspecified"))
      (node (ref "SW9") (pin "2") (pinfunction "2_2") (pintype "input"))
      (node (ref "U1") (pin "3") (pinfunction "GND_3") (pintype "unspecified"))
      (node (ref "U2") (pin "10") (pinfunction "GROUND_10") (pintype "unspecified"))
      (node (ref "U2") (pin "6") (pinfunction "VSS_6") (pintype "unspecified"))
      (node (ref "U3") (pin "12") (pinfunction "VSSA/VREF-_12") (pintype "unspecified"))
      (node (ref "U3") (pin "18") (pinfunction "VSS_18") (pintype "unspecified"))
      (node (ref "U3") (pin "31") (pinfunction "VSS_31") (pintype "unspecified"))
      (node (ref "U3") (pin "47") (pinfunction "VSS_47") (pintype "unspecified"))
      (node (ref "U3") (pin "63") (pinfunction "VSS_63") (pintype "unspecified"))
      (node (ref "U4") (pin "14") (pinfunction "GND_14") (pintype "unspecified"))
      (node (ref "U4") (pin "16") (pinfunction "BRUV_16") (pintype "unspecified"))
      (node (ref "U4") (pin "20") (pinfunction "BRW_20") (pintype "unspecified"))
      (node (ref "U4") (pin "21") (pinfunction "EP_21") (pintype "unspecified"))
      (node (ref "U4") (pin "8") (pinfunction "GND_8") (pintype "unspecified"))
      (node (ref "U4") (pin "9") (pinfunction "GND_9") (pintype "unspecified"))
      (node (ref "U5") (pin "2") (pinfunction "GND_2") (pintype "unspecified"))
      (node (ref "U6") (pin "2") (pinfunction "MODE_2") (pintype "input"))
      (node (ref "U6") (pin "4") (pinfunction "GND_4") (pintype "input"))
      (node (ref "USB1") (pin "A1") (pinfunction "GND_A1") (pintype "unspecified"))
      (node (ref "USB1") (pin "A12") (pinfunction "GND_A12") (pintype "unspecified"))
      (node (ref "USB1") (pin "B1") (pinfunction "GND_B1") (pintype "unspecified"))
      (node (ref "USB1") (pin "B12") (pinfunction "GND_B12") (pintype "unspecified"))
      (node (ref "USB1") (pin "S1") (pinfunction "S1_S1") (pintype "unspecified"))
      (node (ref "X1") (pin "2") (pinfunction "GND_2") (pintype "input"))
      (node (ref "X1") (pin "4") (pinfunction "GND_4") (pintype "input"))
    )
    (net (code "18") (name "I2C_SCL") (class "Default")
      (node (ref "LED19") (pin "1") (pinfunction "SCL_1") (pintype "unspecified"))
      (node (ref "R25") (pin "1") (pinfunction "1_1") (pintype "input"))
      (node (ref "U3") (pin "61") (pinfunction "PB8_61") (pintype "unspecified"))
    )
    (net (code "19") (name "I2C_SDA") (class "Default")
      (node (ref "LED19") (pin "4") (pinfunction "SDA_4") (pintype "unspecified"))
      (node (ref "R26") (pin "1") (pinfunction "1_1") (pintype "input"))
      (node (ref "U3") (pin "62") (pinfunction "PB9_62") (pintype "unspecified"))
    )
    (net (code "20") (name "KEY1") (class "Default")
      (node (ref "C35") (pin "2") (pinfunction "2_2") (pintype "input"))
      (node (ref "R8") (pin "1") (pinfunction "1_1") (pintype "input"))
      (node (ref "SW6") (pin "2") (pinfunction "2_2") (pintype "unspecified"))
      (node (ref "U3") (pin "11") (pinfunction "PC3_11") (pintype "unspecified"))
    )
    (net (code "21") (name "KEY2") (class "Default")
      (node (ref "C29") (pin "2") (pinfunction "2_2") (pintype "input"))
      (node (ref "R3") (pin "1") (pinfunction "1_1") (pintype "input"))
      (node (ref "SW3") (pin "2") (pinfunction "2_2") (pintype "unspecified"))
      (node (ref "U3") (pin "24") (pinfunction "PC4_24") (pintype "unspecified"))
    )
    (net (code "22") (name "KEY3") (class "Default")
      (node (ref "C36") (pin "2") (pinfunction "2_2") (pintype "input"))
      (node (ref "R9") (pin "1") (pinfunction "1_1") (pintype "input"))
      (node (ref "SW7") (pin "2") (pinfunction "2_2") (pintype "unspecified"))
      (node (ref "U3") (pin "10") (pinfunction "PC2_10") (pintype "unspecified"))
    )
    (net (code "23") (name "KEY4") (class "Default")
      (node (ref "C30") (pin "2") (pinfunction "2_2") (pintype "input"))
      (node (ref "R4") (pin "1") (pinfunction "1_1") (pintype "input"))
      (node (ref "SW4") (pin "2") (pinfunction "2_2") (pintype "unspecified"))
      (node (ref "U3") (pin "25") (pinfunction "PC5_25") (pintype "unspecified"))
    )
    (net (code "24") (name "KEY5") (class "Default")
      (node (ref "C37") (pin "2") (pinfunction "2_2") (pintype "input"))
      (node (ref "R10") (pin "1") (pinfunction "1_1") (pintype "input"))
      (node (ref "SW8") (pin "2") (pinfunction "2_2") (pintype "unspecified"))
      (node (ref "U3") (pin "9") (pinfunction "PC1_9") (pintype "unspecified"))
    )
    (net (code "25") (name "KEY6") (class "Default")
      (node (ref "C31") (pin "2") (pinfunction "2_2") (pintype "input"))
      (node (ref "R5") (pin "1") (pinfunction "1_1") (pintype "input"))
      (node (ref "SW5") (pin "2") (pinfunction "2_2") (pintype "unspecified"))
      (node (ref "U3") (pin "8") (pinfunction "PC0_8") (pintype "unspecified"))
    )
    (net (code "26") (name "LED1") (class "Default")
      (node (ref "R22") (pin "1") (pinfunction "1_1") (pintype "input"))
      (node (ref "U3") (pin "56") (pinfunction "PB4_56") (pintype "unspecified"))
    )
    (net (code "27") (name "LED_DATA_3.3V") (class "Default")
      (node (ref "U1") (pin "2") (pinfunction "A_2") (pintype "unspecified"))
      (node (ref "U3") (pin "16") (pinfunction "PA2_16") (pintype "unspecified"))
    )
    (net (code "28") (name "Net-(LED1-DOUT)") (class "Default")
      (node (ref "LED1") (pin "3") (pinfunction "DOUT_3") (pintype "unspecified"))
      (node (ref "LED2") (pin "1") (pinfunction "DIN_1") (pintype "unspecified"))
    )
    (net (code "29") (name "Net-(LED2-DOUT)") (class "Default")
      (node (ref "LED2") (pin "3") (pinfunction "DOUT_3") (pintype "unspecified"))
      (node (ref "LED3") (pin "1") (pinfunction "DIN_1") (pintype "unspecified"))
    )
    (net (code "30") (name "Net-(LED3-DOUT)") (class "Default")
      (node (ref "LED3") (pin "3") (pinfunction "DOUT_3") (pintype "unspecified"))
      (node (ref "LED4") (pin "1") (pinfunction "DIN_1") (pintype "unspecified"))
    )
    (net (code "31") (name "Net-(LED4-DOUT)") (class "Default")
      (node (ref "LED4") (pin "3") (pinfunction "DOUT_3") (pintype "unspecified"))
      (node (ref "LED5") (pin "1") (pinfunction "DIN_1") (pintype "unspecified"))
    )
    (net (code "32") (name "Net-(LED5-DOUT)") (class "Default")
      (node (ref "LED5") (pin "3") (pinfunction "DOUT_3") (pintype "unspecified"))
      (node (ref "LED6") (pin "1") (pinfunction "DIN_1") (pintype "unspecified"))
    )
    (net (code "33") (name "Net-(LED6-DOUT)") (class "Default")
      (node (ref "LED6") (pin "3") (pinfunction "DOUT_3") (pintype "unspecified"))
      (node (ref "LED7") (pin "1") (pinfunction "DIN_1") (pintype "unspecified"))
    )
    (net (code "34") (name "Net-(LED7-DOUT)") (class "Default")
      (node (ref "LED7") (pin "3") (pinfunction "DOUT_3") (pintype "unspecified"))
      (node (ref "LED8") (pin "1") (pinfunction "DIN_1") (pintype "unspecified"))
    )
    (net (code "35") (name "Net-(LED8-DOUT)") (class "Default")
      (node (ref "LED8") (pin "3") (pinfunction "DOUT_3") (pintype "unspecified"))
      (node (ref "LED9") (pin "1") (pinfunction "DIN_1") (pintype "unspecified"))
    )
    (net (code "36") (name "Net-(LED10-DIN)") (class "Default")
      (node (ref "LED10") (pin "1") (pinfunction "DIN_1") (pintype "unspecified"))
      (node (ref "LED9") (pin "3") (pinfunction "DOUT_3") (pintype "unspecified"))
    )
    (net (code "37") (name "Net-(LED10-DOUT)") (class "Default")
      (node (ref "LED10") (pin "3") (pinfunction "DOUT_3") (pintype "unspecified"))
      (node (ref "LED11") (pin "1") (pinfunction "DIN_1") (pintype "unspecified"))
    )
    (net (code "38") (name "Net-(LED11-DOUT)") (class "Default")
      (node (ref "LED11") (pin "3") (pinfunction "DOUT_3") (pintype "unspecified"))
      (node (ref "LED12") (pin "1") (pinfunction "DIN_1") (pintype "unspecified"))
    )
    (net (code "39") (name "Net-(LED12-DOUT)") (class "Default")
      (node (ref "LED12") (pin "3") (pinfunction "DOUT_3") (pintype "unspecified"))
      (node (ref "LED13") (pin "1") (pinfunction "DIN_1") (pintype "unspecified"))
    )
    (net (code "40") (name "Net-(LED13-DOUT)") (class "Default")
      (node (ref "LED13") (pin "3") (pinfunction "DOUT_3") (pintype "unspecified"))
      (node (ref "LED14") (pin "1") (pinfunction "DIN_1") (pintype "unspecified"))
    )
    (net (code "41") (name "Net-(LED14-DOUT)") (class "Default")
      (node (ref "LED14") (pin "3") (pinfunction "DOUT_3") (pintype "unspecified"))
      (node (ref "LED15") (pin "1") (pinfunction "DIN_1") (pintype "unspecified"))
    )
    (net (code "42") (name "Net-(LED16-K)") (class "Default")
      (node (ref "LED16") (pin "2") (pinfunction "K_2") (pintype "unspecified"))
      (node (ref "R21") (pin "2") (pinfunction "2_2") (pintype "input"))
    )
    (net (code "43") (name "Net-(LED17-K)") (class "Default")
      (node (ref "LED17") (pin "2") (pinfunction "K_2") (pintype "unspecified"))
      (node (ref "R22") (pin "2") (pinfunction "2_2") (pintype "input"))
    )
    (net (code "44") (name "Net-(U3-BOOT0)") (class "Default")
      (node (ref "R11") (pin "2") (pinfunction "2_2") (pintype "input"))
      (node (ref "U3") (pin "60") (pinfunction "BOOT0_60") (pintype "unspecified"))
    )
    (net (code "45") (name "Net-(U3-PH0-OSC_IN)") (class "Default")
      (node (ref "C32") (pin "1") (pinfunction "1_1") (pintype "input"))
      (node (ref "U3") (pin "5") (pinfunction "PH0-OSC_IN_5") (pintype "unspecified"))
      (node (ref "X1") (pin "3") (pinfunction "2_3") (pintype "input"))
    )
    (net (code "46") (name "Net-(U3-PH1-OSC_OUT)") (class "Default")
      (node (ref "C34") (pin "1") (pinfunction "1_1") (pintype "input"))
      (node (ref "U3") (pin "6") (pinfunction "PH1-OSC_OUT_6") (pintype "unspecified"))
      (node (ref "X1") (pin "1") (pinfunction "1_1") (pintype "input"))
    )
    (net (code "47") (name "Net-(U3-VCAP_1)") (class "Default")
      (node (ref "C39") (pin "2") (pinfunction "2_2") (pintype "input"))
      (node (ref "U3") (pin "30") (pinfunction "VCAP_1_30") (pintype "unspecified"))
    )
    (net (code "48") (name "Net-(U4-1.8VOUT)") (class "Default")
      (node (ref "C45") (pin "2") (pinfunction "2_2") (pintype "unspecified"))
      (node (ref "U4") (pin "13") (pinfunction "1.8VOUT_13") (pintype "unspecified"))
    )
    (net (code "49") (name "Net-(U4-VCP)") (class "Default")
      (node (ref "C40") (pin "1") (pinfunction "1_1") (pintype "input"))
      (node (ref "U4") (pin "2") (pinfunction "VCP_2") (pintype "unspecified"))
    )
    (net (code "50") (name "Net-(U4-VIO{slash}NSTDBY)") (class "Default")
      (node (ref "C46") (pin "2") (pinfunction "2_2") (pintype "unspecified"))
      (node (ref "U4") (pin "11") (pinfunction "VIO/NSTDBY_11") (pintype "unspecified"))
    )
    (net (code "51") (name "Net-(U5-EN)") (class "Default")
      (node (ref "C47") (pin "2") (pinfunction "2_2") (pintype "unspecified"))
      (node (ref "C48") (pin "2") (pinfunction "2_2") (pintype "input"))
      (node (ref "L4") (pin "2") (pinfunction "2_2") (pintype "unspecified"))
      (node (ref "U5") (pin "1") (pinfunction "IN_1") (pintype "unspecified"))
      (node (ref "U5") (pin "3") (pinfunction "EN_3") (pintype "unspecified"))
    )
    (net (code "52") (name "Net-(USB1-CC1)") (class "Default")
      (node (ref "R14") (pin "2") (pinfunction "2_2") (pintype "input"))
      (node (ref "USB1") (pin "A5") (pinfunction "CC1_A5") (pintype "unspecified"))
    )
    (net (code "53") (name "Net-(USB1-CC2)") (class "Default")
      (node (ref "R13") (pin "2") (pinfunction "2_2") (pintype "input"))
      (node (ref "USB1") (pin "B5") (pinfunction "CC2_B5") (pintype "unspecified"))
    )
    (net (code "54") (name "RES") (class "Default")
      (node (ref "H3") (pin "5") (pinfunction "5_5") (pintype "input"))
      (node (ref "U3") (pin "35") (pinfunction "PB14_35") (pintype "unspecified"))
    )
    (net (code "55") (name "SDMMC1_CD_GPIO") (class "Default")
      (node (ref "C33") (pin "2") (pinfunction "2_2") (pintype "input"))
      (node (ref "R6") (pin "1") (pinfunction "1_1") (pintype "input"))
      (node (ref "U2") (pin "9") (pinfunction "CARD_DETECT_9") (pintype "unspecified"))
      (node (ref "U3") (pin "50") (pinfunction "PA15_50") (pintype "unspecified"))
    )
    (net (code "56") (name "SDMMC1_CLK") (class "Default")
      (node (ref "R7") (pin "1") (pinfunction "1_1") (pintype "input"))
      (node (ref "U3") (pin "53") (pinfunction "PC12_53") (pintype "unspecified"))
    )
    (net (code "57") (name "SDMMC1_CMD") (class "Default")
      (node (ref "L2") (pin "4") (pinfunction "Ch4_In_4") (pintype "unspecified"))
      (node (ref "U2") (pin "3") (pinfunction "CMD_3") (pintype "unspecified"))
      (node (ref "U3") (pin "54") (pinfunction "PD2_54") (pintype "unspecified"))
    )
    (net (code "58") (name "SDMMC1_D0") (class "Default")
      (node (ref "L2") (pin "2") (pinfunction "Ch2_In_2") (pintype "unspecified"))
      (node (ref "U2") (pin "7") (pinfunction "DAT0_7") (pintype "unspecified"))
      (node (ref "U3") (pin "39") (pinfunction "PC8_39") (pintype "unspecified"))
    )
    (net (code "59") (name "SDMMC1_D1") (class "Default")
      (node (ref "L2") (pin "1") (pinfunction "Ch1_In_1") (pintype "unspecified"))
      (node (ref "U2") (pin "8") (pinfunction "DAT1_8") (pintype "unspecified"))
      (node (ref "U3") (pin "40") (pinfunction "PC9_40") (pintype "unspecified"))
    )
    (net (code "60") (name "SDMMC1_D2") (class "Default")
      (node (ref "L2") (pin "6") (pinfunction "Ch6_In_6") (pintype "unspecified"))
      (node (ref "U2") (pin "1") (pinfunction "DAT2_1") (pintype "unspecified"))
      (node (ref "U3") (pin "51") (pinfunction "PC10_51") (pintype "unspecified"))
    )
    (net (code "61") (name "SDMMC1_D3") (class "Default")
      (node (ref "L2") (pin "5") (pinfunction "Ch5_In_5") (pintype "unspecified"))
      (node (ref "U2") (pin "2") (pinfunction "CD/DAT3_2") (pintype "unspecified"))
      (node (ref "U3") (pin "52") (pinfunction "PC11_52") (pintype "unspecified"))
    )
    (net (code "62") (name "SPI2_MOSI") (class "Default")
      (node (ref "H3") (pin "4") (pinfunction "4_4") (pintype "input"))
      (node (ref "U3") (pin "36") (pinfunction "PB15_36") (pintype "unspecified"))
    )
    (net (code "63") (name "SPI2_SCL") (class "Default")
      (node (ref "H3") (pin "3") (pinfunction "3_3") (pintype "input"))
      (node (ref "U3") (pin "34") (pinfunction "PB13_34") (pintype "unspecified"))
    )
    (net (code "64") (name "SWCLK") (class "Default")
      (node (ref "H2") (pin "2") (pinfunction "2_2") (pintype "unspecified"))
      (node (ref "U3") (pin "49") (pinfunction "PA14_49") (pintype "unspecified"))
    )
    (net (code "65") (name "SWDIO") (class "Default")
      (node (ref "H2") (pin "3") (pinfunction "3_3") (pintype "unspecified"))
      (node (ref "U3") (pin "46") (pinfunction "PA13_46") (pintype "unspecified"))
    )
    (net (code "66") (name "U") (class "Default")
      (node (ref "H4") (pin "1") (pinfunction "1_1") (pintype "unspecified"))
      (node (ref "U4") (pin "15") (pinfunction "U_15") (pintype "unspecified"))
    )
    (net (code "67") (name "UH") (class "Default")
      (node (ref "R15") (pin "2") (pinfunction "2_2") (pintype "input"))
      (node (ref "U3") (pin "41") (pinfunction "PA8_41") (pintype "unspecified"))
      (node (ref "U4") (pin "3") (pinfunction "UH_3") (pintype "unspecified"))
    )
    (net (code "68") (name "UL") (class "Default")
      (node (ref "R18") (pin "2") (pinfunction "2_2") (pintype "input"))
      (node (ref "U3") (pin "23") (pinfunction "PA7_23") (pintype "unspecified"))
      (node (ref "U4") (pin "6") (pinfunction "UL_6") (pintype "unspecified"))
    )
    (net (code "69") (name "USART1_RX") (class "Default")
      (node (ref "H1") (pin "2") (pinfunction "2_2") (pintype "unspecified"))
      (node (ref "U3") (pin "59") (pinfunction "PB7_59") (pintype "unspecified"))
    )
    (net (code "70") (name "USART1_TX") (class "Default")
      (node (ref "H1") (pin "1") (pinfunction "1_1") (pintype "unspecified"))
      (node (ref "U3") (pin "58") (pinfunction "PB6_58") (pintype "unspecified"))
    )
    (net (code "71") (name "USB_DM") (class "Default")
      (node (ref "D1") (pin "4") (pinfunction "I/O2_4") (pintype "unspecified"))
      (node (ref "U3") (pin "44") (pinfunction "PA11_44") (pintype "unspecified"))
    )
    (net (code "72") (name "USB_DP") (class "Default")
      (node (ref "D1") (pin "6") (pinfunction "I/O1_6") (pintype "unspecified"))
      (node (ref "U3") (pin "45") (pinfunction "PA12_45") (pintype "unspecified"))
    )
    (net (code "73") (name "V") (class "Default")
      (node (ref "H4") (pin "2") (pinfunction "2_2") (pintype "unspecified"))
      (node (ref "U4") (pin "17") (pinfunction "V_17") (pintype "unspecified"))
    )
    (net (code "74") (name "VH") (class "Default")
      (node (ref "R16") (pin "2") (pinfunction "2_2") (pintype "input"))
      (node (ref "U3") (pin "42") (pinfunction "PA9_42") (pintype "unspecified"))
      (node (ref "U4") (pin "4") (pinfunction "VH_4") (pintype "unspecified"))
    )
    (net (code "75") (name "VL") (class "Default")
      (node (ref "R20") (pin "2") (pinfunction "2_2") (pintype "input"))
      (node (ref "U3") (pin "26") (pinfunction "PB0_26") (pintype "unspecified"))
      (node (ref "U4") (pin "10") (pinfunction "VL_10") (pintype "unspecified"))
    )
    (net (code "76") (name "W") (class "Default")
      (node (ref "H4") (pin "3") (pinfunction "3_3") (pintype "unspecified"))
      (node (ref "U4") (pin "1") (pinfunction "W_1") (pintype "unspecified"))
    )
    (net (code "77") (name "WH") (class "Default")
      (node (ref "R17") (pin "2") (pinfunction "2_2") (pintype "input"))
      (node (ref "U3") (pin "43") (pinfunction "PA10_43") (pintype "unspecified"))
      (node (ref "U4") (pin "5") (pinfunction "WH_5") (pintype "unspecified"))
    )
    (net (code "78") (name "WL") (class "Default")
      (node (ref "R19") (pin "2") (pinfunction "2_2") (pintype "input"))
      (node (ref "U3") (pin "27") (pinfunction "PB1_27") (pintype "unspecified"))
      (node (ref "U4") (pin "7") (pinfunction "WL_7") (pintype "unspecified"))
    )
    (net (code "79") (name "Z") (class "Default")
      (node (ref "R24") (pin "1") (pinfunction "1_1") (pintype "input"))
      (node (ref "U3") (pin "21") (pinfunction "PA5_21") (pintype "unspecified"))
      (node (ref "U6") (pin "8") (pinfunction "Z_8") (pintype "input"))
    )
    (net (code "80") (name "unconnected-(LED15-DOUT-Pad3)") (class "Default")
      (node (ref "LED15") (pin "3") (pinfunction "DOUT_3") (pintype "unspecified+no_connect"))
    )
    (net (code "81") (name "unconnected-(SCREW1-Pad1)") (class "Default")
      (node (ref "SCREW1") (pin "1") (pinfunction "1_1") (pintype "input+no_connect"))
    )
    (net (code "82") (name "unconnected-(SCREW2-Pad1)") (class "Default")
      (node (ref "SCREW2") (pin "1") (pinfunction "1_1") (pintype "input+no_connect"))
    )
    (net (code "83") (name "unconnected-(SCREW3-Pad1)") (class "Default")
      (node (ref "SCREW3") (pin "1") (pinfunction "1_1") (pintype "input+no_connect"))
    )
    (net (code "84") (name "unconnected-(SCREW4-Pad1)") (class "Default")
      (node (ref "SCREW4") (pin "1") (pinfunction "1_1") (pintype "input+no_connect"))
    )
    (net (code "85") (name "unconnected-(SCREW5-Pad1)") (class "Default")
      (node (ref "SCREW5") (pin "1") (pinfunction "1_1") (pintype "input+no_connect"))
    )
    (net (code "86") (name "unconnected-(SCREW6-Pad1)") (class "Default")
      (node (ref "SCREW6") (pin "1") (pinfunction "1_1") (pintype "input+no_connect"))
    )
    (net (code "87") (name "unconnected-(SCREW7-Pad1)") (class "Default")
      (node (ref "SCREW7") (pin "1") (pinfunction "1_1") (pintype "input+no_connect"))
    )
    (net (code "88") (name "unconnected-(SCREW8-Pad1)") (class "Default")
      (node (ref "SCREW8") (pin "1") (pinfunction "1_1") (pintype "input+no_connect"))
    )
    (net (code "89") (name "unconnected-(SW1-Pad1)") (class "Default")
      (node (ref "SW1") (pin "1") (pinfunction "1_1") (pintype "unspecified+no_connect"))
    )
    (net (code "90") (name "unconnected-(SW1-Pad3)") (class "Default")
      (node (ref "SW1") (pin "3") (pinfunction "3_3") (pintype "unspecified+no_connect"))
    )
    (net (code "91") (name "unconnected-(SW2-Pad1)") (class "Default")
      (node (ref "SW2") (pin "1") (pinfunction "1_1") (pintype "unspecified+no_connect"))
    )
    (net (code "92") (name "unconnected-(SW2-Pad3)") (class "Default")
      (node (ref "SW2") (pin "3") (pinfunction "3_3") (pintype "unspecified+no_connect"))
    )
    (net (code "93") (name "unconnected-(U1-NC-Pad1)") (class "Default")
      (node (ref "U1") (pin "1") (pinfunction "NC_1") (pintype "unspecified+no_connect"))
    )
    (net (code "94") (name "unconnected-(U3-PA3-Pad17)") (class "Default")
      (node (ref "U3") (pin "17") (pinfunction "PA3_17") (pintype "unspecified"))
    )
    (net (code "95") (name "unconnected-(U3-PA4-Pad20)") (class "Default")
      (node (ref "U3") (pin "20") (pinfunction "PA4_20") (pintype "unspecified"))
    )
    (net (code "96") (name "unconnected-(U3-PA6-Pad22)") (class "Default")
      (node (ref "U3") (pin "22") (pinfunction "PA6_22") (pintype "unspecified"))
    )
    (net (code "97") (name "unconnected-(U3-PB3-Pad55)") (class "Default")
      (node (ref "U3") (pin "55") (pinfunction "PB3_55") (pintype "unspecified"))
    )
    (net (code "98") (name "unconnected-(U3-PB5-Pad57)") (class "Default")
      (node (ref "U3") (pin "57") (pinfunction "PB5_57") (pintype "unspecified"))
    )
    (net (code "99") (name "unconnected-(U3-PC13-TAMPER-RTC-Pad2)") (class "Default")
      (node (ref "U3") (pin "2") (pinfunction "PC13-TAMPER-RTC_2") (pintype "unspecified"))
    )
    (net (code "100") (name "unconnected-(U3-PC14-OSC32_IN-Pad3)") (class "Default")
      (node (ref "U3") (pin "3") (pinfunction "PC14-OSC32_IN_3") (pintype "unspecified"))
    )
    (net (code "101") (name "unconnected-(U3-PC15-OSC32_OUT-Pad4)") (class "Default")
      (node (ref "U3") (pin "4") (pinfunction "PC15-OSC32_OUT_4") (pintype "unspecified"))
    )
    (net (code "102") (name "unconnected-(U4-NC-Pad19)") (class "Default")
      (node (ref "U4") (pin "19") (pinfunction "NC_19") (pintype "unspecified+no_connect"))
    )
    (net (code "103") (name "unconnected-(U5-NC-Pad4)") (class "Default")
      (node (ref "U5") (pin "4") (pinfunction "NC_4") (pintype "unspecified+no_connect"))
    )
    (net (code "104") (name "unconnected-(U6-OUT-Pad3)") (class "Default")
      (node (ref "U6") (pin "3") (pinfunction "OUT_3") (pintype "input+no_connect"))
    )
    (net (code "105") (name "unconnected-(U6-PUSH-Pad5)") (class "Default")
      (node (ref "U6") (pin "5") (pinfunction "PUSH_5") (pintype "input+no_connect"))
    )
    (net (code "106") (name "unconnected-(USB1-SBU1-PadA8)") (class "Default")
      (node (ref "USB1") (pin "A8") (pinfunction "SBU1_A8") (pintype "unspecified+no_connect"))
    )
    (net (code "107") (name "unconnected-(USB1-SBU2-PadB8)") (class "Default")
      (node (ref "USB1") (pin "B8") (pinfunction "SBU2_B8") (pintype "unspecified+no_connect"))
    )
    (net (code "108") (name "{slash}RESET") (class "Default")
      (node (ref "C38") (pin "2") (pinfunction "2_2") (pintype "input"))
      (node (ref "R12") (pin "1") (pinfunction "1_1") (pintype "input"))
      (node (ref "SW9") (pin "1") (pinfunction "1_1") (pintype "input"))
      (node (ref "U3") (pin "7") (pinfunction "NRST_7") (pintype "unspecified"))
    )
  )
)
